# 2313.net
KiCad netlist of a schematic drawn in EAGLE
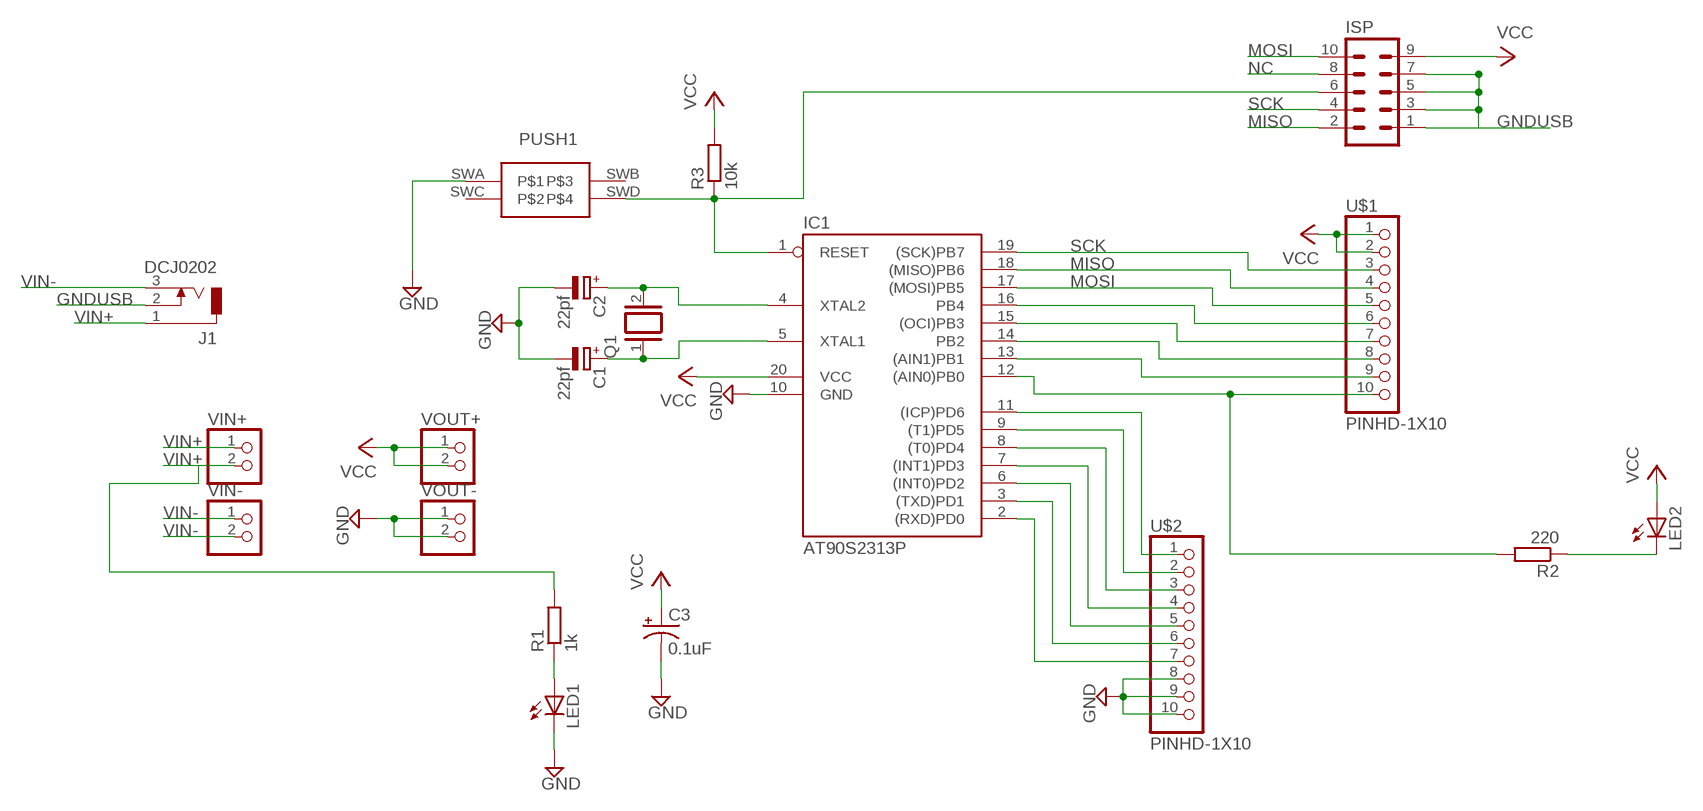
[diagram p0: schematic, sheet 1]

(export (version "E")
  (design (tool "Eeschema 10.0.6"))
  (components
    (comp (ref "C1")
      (value "22pf")
      (footprint "eagle-import:E1,8-4")
      (libsource (lib "eagle-import") (part "CPOL-EUE1.8-4"))
    )
    (comp (ref "C2")
      (value "22pf")
      (footprint "eagle-import:E1,8-4")
      (libsource (lib "eagle-import") (part "CPOL-EUE1.8-4"))
    )
    (comp (ref "C3")
      (value "0.1uF")
      (footprint "eagle-import:E1,8-4")
      (libsource (lib "eagle-import") (part "CPOL-USE1.8-4"))
    )
    (comp (ref "IC1")
      (value "AT90S2313P")
      (footprint "eagle-import:DIL20")
      (libsource (lib "eagle-import") (part "AT90S2313P"))
    )
    (comp (ref "ISP")
      (value "MA05-2")
      (footprint "eagle-import:MA05-2")
      (libsource (lib "eagle-import") (part "MA05-2"))
    )
    (comp (ref "J1")
      (value "DCJ0202")
      (footprint "eagle-import:DCJ0202")
      (libsource (lib "eagle-import") (part "DCJ0202"))
    )
    (comp (ref "LED1")
      (value "LED3MM")
      (footprint "eagle-import:LED3MM")
      (libsource (lib "eagle-import") (part "LED3MM"))
    )
    (comp (ref "LED2")
      (value "LED3MM")
      (footprint "eagle-import:LED3MM")
      (libsource (lib "eagle-import") (part "LED3MM"))
    )
    (comp (ref "PUSH1")
      (value "PUSH_BUTTON")
      (footprint "eagle-import:PUSH_BUTTON")
      (libsource (lib "eagle-import") (part "PUSH_BUTTON"))
    )
    (comp (ref "Q1")
      (value "XTAL")
      (footprint "eagle-import:Q")
      (libsource (lib "eagle-import") (part "XTAL"))
    )
    (comp (ref "R1")
      (value "1k")
      (footprint "eagle-import:0204_7")
      (libsource (lib "eagle-import") (part "R-EU_0204/7"))
    )
    (comp (ref "R2")
      (value "220")
      (footprint "eagle-import:0204_7")
      (libsource (lib "eagle-import") (part "R-EU_0204/7"))
    )
    (comp (ref "R3")
      (value "10k")
      (footprint "eagle-import:0204_7")
      (libsource (lib "eagle-import") (part "R-EU_0204/7"))
    )
    (comp (ref "U$1")
      (value "PINHD-1X10")
      (footprint "eagle-import:1X10-BIG")
      (libsource (lib "eagle-import") (part "PINHD-1X10"))
    )
    (comp (ref "U$2")
      (value "PINHD-1X10")
      (footprint "eagle-import:1X10-BIG")
      (libsource (lib "eagle-import") (part "PINHD-1X10"))
    )
    (comp (ref "VIN+")
      (value "PINHD-1X2")
      (footprint "eagle-import:1X02")
      (libsource (lib "eagle-import") (part "PINHD-1X2"))
    )
    (comp (ref "VIN-")
      (value "PINHD-1X2")
      (footprint "eagle-import:1X02")
      (libsource (lib "eagle-import") (part "PINHD-1X2"))
    )
    (comp (ref "VOUT+")
      (value "PINHD-1X2")
      (footprint "eagle-import:1X02")
      (libsource (lib "eagle-import") (part "PINHD-1X2"))
    )
    (comp (ref "VOUT-")
      (value "PINHD-1X2")
      (footprint "eagle-import:1X02")
      (libsource (lib "eagle-import") (part "PINHD-1X2"))
    )
  )
  (nets
    (net (code "1") (name "/GNDUSB") (class "Default")
      (node (ref "ISP") (pin "1") (pinfunction "1_1") (pintype "passive"))
      (node (ref "ISP") (pin "3") (pinfunction "3_3") (pintype "passive"))
      (node (ref "ISP") (pin "5") (pinfunction "5_5") (pintype "passive"))
      (node (ref "ISP") (pin "7") (pinfunction "7_7") (pintype "passive"))
      (node (ref "J1") (pin "2") (pinfunction "2_2") (pintype "passive"))
    )
    (net (code "2") (name "/MISO") (class "Default")
      (node (ref "IC1") (pin "18") (pinfunction "(MISO)PB6_18") (pintype "bidirectional"))
      (node (ref "ISP") (pin "2") (pinfunction "2_2") (pintype "passive"))
      (node (ref "U$1") (pin "4") (pinfunction "4_4") (pintype "passive"))
    )
    (net (code "3") (name "/MOSI") (class "Default")
      (node (ref "IC1") (pin "17") (pinfunction "(MOSI)PB5_17") (pintype "bidirectional"))
      (node (ref "ISP") (pin "10") (pinfunction "10_10") (pintype "passive"))
      (node (ref "U$1") (pin "5") (pinfunction "5_5") (pintype "passive"))
    )
    (net (code "4") (name "/NC") (class "Default")
      (node (ref "ISP") (pin "8") (pinfunction "8_8") (pintype "passive"))
    )
    (net (code "5") (name "/SCK") (class "Default")
      (node (ref "IC1") (pin "19") (pinfunction "(SCK)PB7_19") (pintype "bidirectional"))
      (node (ref "ISP") (pin "4") (pinfunction "4_4") (pintype "passive"))
      (node (ref "U$1") (pin "3") (pinfunction "3_3") (pintype "passive"))
    )
    (net (code "6") (name "/VIN+") (class "Default")
      (node (ref "J1") (pin "1") (pinfunction "1_1") (pintype "passive"))
      (node (ref "R1") (pin "2") (pinfunction "2_2") (pintype "passive"))
      (node (ref "VIN+") (pin "1") (pinfunction "1_1") (pintype "passive"))
      (node (ref "VIN+") (pin "2") (pinfunction "2_2") (pintype "passive"))
    )
    (net (code "7") (name "/VIN-") (class "Default")
      (node (ref "J1") (pin "3") (pinfunction "3_3") (pintype "passive"))
      (node (ref "VIN-") (pin "1") (pinfunction "1_1") (pintype "passive"))
      (node (ref "VIN-") (pin "2") (pinfunction "2_2") (pintype "passive"))
    )
    (net (code "8") (name "GND") (class "Default")
      (node (ref "C1") (pin "-") (pinfunction "-_-") (pintype "passive"))
      (node (ref "C2") (pin "-") (pinfunction "-_-") (pintype "passive"))
      (node (ref "C3") (pin "-") (pinfunction "-_-") (pintype "passive"))
      (node (ref "IC1") (pin "10") (pinfunction "GND_10") (pintype "power_in"))
      (node (ref "LED1") (pin "K") (pinfunction "C_K") (pintype "passive"))
      (node (ref "PUSH1") (pin "SWA") (pinfunction "P$1_SWA") (pintype "bidirectional"))
      (node (ref "U$2") (pin "10") (pinfunction "10_10") (pintype "passive"))
      (node (ref "U$2") (pin "8") (pinfunction "8_8") (pintype "passive"))
      (node (ref "U$2") (pin "9") (pinfunction "9_9") (pintype "passive"))
      (node (ref "VOUT-") (pin "1") (pinfunction "1_1") (pintype "passive"))
      (node (ref "VOUT-") (pin "2") (pinfunction "2_2") (pintype "passive"))
    )
    (net (code "9") (name "Net-(IC1-(AIN0)PB0)") (class "Default")
      (node (ref "IC1") (pin "12") (pinfunction "(AIN0)PB0_12") (pintype "bidirectional"))
      (node (ref "R2") (pin "2") (pinfunction "2_2") (pintype "passive"))
      (node (ref "U$1") (pin "10") (pinfunction "10_10") (pintype "passive"))
    )
    (net (code "10") (name "Net-(IC1-(AIN1)PB1)") (class "Default")
      (node (ref "IC1") (pin "13") (pinfunction "(AIN1)PB1_13") (pintype "bidirectional"))
      (node (ref "U$1") (pin "9") (pinfunction "9_9") (pintype "passive"))
    )
    (net (code "11") (name "Net-(IC1-(ICP)PD6)") (class "Default")
      (node (ref "IC1") (pin "11") (pinfunction "(ICP)PD6_11") (pintype "bidirectional"))
      (node (ref "U$2") (pin "1") (pinfunction "1_1") (pintype "passive"))
    )
    (net (code "12") (name "Net-(IC1-(INT0)PD2)") (class "Default")
      (node (ref "IC1") (pin "6") (pinfunction "(INT0)PD2_6") (pintype "bidirectional"))
      (node (ref "U$2") (pin "5") (pinfunction "5_5") (pintype "passive"))
    )
    (net (code "13") (name "Net-(IC1-(INT1)PD3)") (class "Default")
      (node (ref "IC1") (pin "7") (pinfunction "(INT1)PD3_7") (pintype "bidirectional"))
      (node (ref "U$2") (pin "4") (pinfunction "4_4") (pintype "passive"))
    )
    (net (code "14") (name "Net-(IC1-(OCI)PB3)") (class "Default")
      (node (ref "IC1") (pin "15") (pinfunction "(OCI)PB3_15") (pintype "bidirectional"))
      (node (ref "U$1") (pin "7") (pinfunction "7_7") (pintype "passive"))
    )
    (net (code "15") (name "Net-(IC1-(RXD)PD0)") (class "Default")
      (node (ref "IC1") (pin "2") (pinfunction "(RXD)PD0_2") (pintype "bidirectional"))
      (node (ref "U$2") (pin "7") (pinfunction "7_7") (pintype "passive"))
    )
    (net (code "16") (name "Net-(IC1-(T0)PD4)") (class "Default")
      (node (ref "IC1") (pin "8") (pinfunction "(T0)PD4_8") (pintype "bidirectional"))
      (node (ref "U$2") (pin "3") (pinfunction "3_3") (pintype "passive"))
    )
    (net (code "17") (name "Net-(IC1-(T1)PD5)") (class "Default")
      (node (ref "IC1") (pin "9") (pinfunction "(T1)PD5_9") (pintype "bidirectional"))
      (node (ref "U$2") (pin "2") (pinfunction "2_2") (pintype "passive"))
    )
    (net (code "18") (name "Net-(IC1-(TXD)PD1)") (class "Default")
      (node (ref "IC1") (pin "3") (pinfunction "(TXD)PD1_3") (pintype "bidirectional"))
      (node (ref "U$2") (pin "6") (pinfunction "6_6") (pintype "passive"))
    )
    (net (code "19") (name "Net-(IC1-PB2)") (class "Default")
      (node (ref "IC1") (pin "14") (pinfunction "PB2_14") (pintype "bidirectional"))
      (node (ref "U$1") (pin "8") (pinfunction "8_8") (pintype "passive"))
    )
    (net (code "20") (name "Net-(IC1-PB4)") (class "Default")
      (node (ref "IC1") (pin "16") (pinfunction "PB4_16") (pintype "bidirectional"))
      (node (ref "U$1") (pin "6") (pinfunction "6_6") (pintype "passive"))
    )
    (net (code "21") (name "Net-(IC1-RESET)") (class "Default")
      (node (ref "IC1") (pin "1") (pinfunction "RESET_1") (pintype "bidirectional"))
      (node (ref "ISP") (pin "6") (pinfunction "6_6") (pintype "passive"))
      (node (ref "PUSH1") (pin "SWD") (pinfunction "P$4_SWD") (pintype "bidirectional"))
      (node (ref "R3") (pin "1") (pinfunction "1_1") (pintype "passive"))
    )
    (net (code "22") (name "Net-(IC1-XTAL1)") (class "Default")
      (node (ref "C1") (pin "+") (pinfunction "+_+") (pintype "passive"))
      (node (ref "IC1") (pin "5") (pinfunction "XTAL1_5") (pintype "bidirectional"))
      (node (ref "Q1") (pin "1") (pinfunction "1_1") (pintype "passive"))
    )
    (net (code "23") (name "Net-(IC1-XTAL2)") (class "Default")
      (node (ref "C2") (pin "+") (pinfunction "+_+") (pintype "passive"))
      (node (ref "IC1") (pin "4") (pinfunction "XTAL2_4") (pintype "bidirectional"))
      (node (ref "Q1") (pin "2") (pinfunction "2_2") (pintype "passive"))
    )
    (net (code "24") (name "Net-(LED1-PadA)") (class "Default")
      (node (ref "LED1") (pin "A") (pinfunction "A_A") (pintype "passive"))
      (node (ref "R1") (pin "1") (pinfunction "1_1") (pintype "passive"))
    )
    (net (code "25") (name "Net-(LED2-C)") (class "Default")
      (node (ref "LED2") (pin "K") (pinfunction "C_K") (pintype "passive"))
      (node (ref "R2") (pin "1") (pinfunction "1_1") (pintype "passive"))
    )
    (net (code "26") (name "VCC") (class "Default")
      (node (ref "C3") (pin "+") (pinfunction "+_+") (pintype "passive"))
      (node (ref "IC1") (pin "20") (pinfunction "VCC_20") (pintype "power_in"))
      (node (ref "ISP") (pin "9") (pinfunction "9_9") (pintype "passive"))
      (node (ref "LED2") (pin "A") (pinfunction "A_A") (pintype "passive"))
      (node (ref "R3") (pin "2") (pinfunction "2_2") (pintype "passive"))
      (node (ref "U$1") (pin "1") (pinfunction "1_1") (pintype "passive"))
      (node (ref "U$1") (pin "2") (pinfunction "2_2") (pintype "passive"))
      (node (ref "VOUT+") (pin "1") (pinfunction "1_1") (pintype "passive"))
      (node (ref "VOUT+") (pin "2") (pinfunction "2_2") (pintype "passive"))
    )
    (net (code "27") (name "unconnected-(PUSH1-P$2-PadSWC)") (class "Default")
      (node (ref "PUSH1") (pin "SWC") (pinfunction "P$2_SWC") (pintype "bidirectional"))
    )
    (net (code "28") (name "unconnected-(PUSH1-P$3-PadSWB)") (class "Default")
      (node (ref "PUSH1") (pin "SWB") (pinfunction "P$3_SWB") (pintype "bidirectional"))
    )
  )
)
